# SparkaAway.net
KiCad netlist of a schematic drawn in Altium Designer
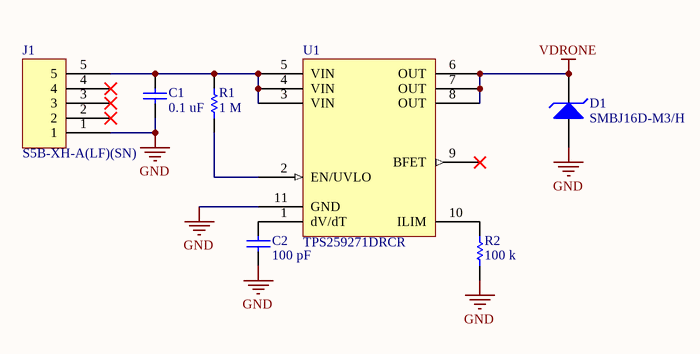
[diagram p0: SparkaAway.SchDoc]

(export (version "E")
  (design (tool "Eeschema 10.0.6"))
  (components
    (comp (ref "C1")
      (value "0.1 uF")
      (footprint "CAPC1608X10L")
      (description "CAP CER 0.1UF 50V X7R 0603")
      (fields
        (field (name "MANUFACTURER") "Samsung Electro-Mechanics America, Inc.")
        (field (name "MANUFACTURER PART NUMBER") "CL10B104MB8NNNC")
      )
      (libsource (lib "Componentes") (part "CL10B104MB8NNNC"))
    )
    (comp (ref "C2")
      (value "100 pF")
      (footprint "CAPC1608X10L")
      (description "Multilayer Ceramic Capacitors MLCC - SMD/SMT 0603 100pF 50volts C0G 5% T=0.8mm")
      (fields
        (field (name "MANUFACTURER") "TDK")
        (field (name "MANUFACTURER PART NUMBER") "CGA3E2C0G1H101J080AA")
      )
      (libsource (lib "Componentes") (part "CGA3E2C0G1H101J080AA"))
    )
    (comp (ref "D1")
      (value "SMBJ16D-M3/H")
      (footprint "DO-214AA SMB DIOM4336X24N")
      (description "TVS DIODE 16VWM 25.6VC DO214AA")
      (fields (field (name "MANUFACTURER") "Vishay Semiconductor Diodes Division"))
      (libsource (lib "SparkAway") (part "SMBJ16D-M3/H"))
    )
    (comp (ref "J1")
      (value "S5B-XH-A(LF)(SN)")
      (footprint "S5B-XH-A(LF)(SN)")
      (description "CONN HEADER XH SIDE 5POS 2.5MM")
      (fields (field (name "MANUFACTURER") "JST Sales America Inc."))
      (libsource (lib "SparkAway") (part "S5B-XH-A(LF)(SN)"))
    )
    (comp (ref "R1")
      (value "1 M")
      (footprint "RESC1608X05N")
      (description "Thick Film Resistors - SMD 1/10watt 1.0Mohms 1%")
      (fields
        (field (name "MANUFACTURER") "Vishay / Dale")
        (field (name "MANUFACTURER PART NUMBER") "CRCW06031M00FKEA")
      )
      (libsource (lib "Componentes") (part "CRCW06031M00FKEA"))
    )
    (comp (ref "R2")
      (value "100 k")
      (footprint "RESC1608X05N")
      (description "Thick Film Resistors - SMD 1/10watt 100Kohms 1%")
      (fields
        (field (name "MANUFACTURER") "Vishay / Dale")
        (field (name "MANUFACTURER PART NUMBER") "CRCW0603100KFKEA")
      )
      (libsource (lib "Componentes") (part "CRCW0603100KFKEA"))
    )
    (comp (ref "U1")
      (value "TPS259271DRCR")
      (footprint "TI S-PVSON-N10 SON50P300X100_HS-11N")
      (description "IC EFUSE 18V BFET DVR 5A 10VSON")
      (fields (field (name "MANUFACTURER") "Texas Instruments"))
      (libsource (lib "SparkAway") (part "TPS259271DRCR"))
    )
  )
  (nets
    (net (code "1") (name "GND") (class "Default")
      (node (ref "C1") (pin "1") (pinfunction "1_1") (pintype "passive"))
      (node (ref "C2") (pin "1") (pinfunction "1_1") (pintype "passive"))
      (node (ref "D1") (pin "2") (pinfunction "A_2") (pintype "passive"))
      (node (ref "J1") (pin "1") (pinfunction "1_1") (pintype "passive"))
      (node (ref "R2") (pin "1") (pinfunction "1_1") (pintype "passive"))
      (node (ref "U1") (pin "11") (pinfunction "GND_11") (pintype "power_in"))
    )
    (net (code "2") (name "Net-(C1-Pad2)") (class "Default")
      (node (ref "C1") (pin "2") (pinfunction "2_2") (pintype "passive"))
      (node (ref "J1") (pin "5") (pinfunction "5_5") (pintype "passive"))
      (node (ref "R1") (pin "2") (pinfunction "2_2") (pintype "passive"))
      (node (ref "U1") (pin "3") (pinfunction "VIN_3") (pintype "power_in"))
      (node (ref "U1") (pin "4") (pinfunction "VIN_4") (pintype "power_in"))
      (node (ref "U1") (pin "5") (pinfunction "VIN_5") (pintype "power_in"))
    )
    (net (code "3") (name "Net-(U1-EN{slash}UVLO)") (class "Default")
      (node (ref "R1") (pin "1") (pinfunction "1_1") (pintype "passive"))
      (node (ref "U1") (pin "2") (pinfunction "EN/UVLO_2") (pintype "input"))
    )
    (net (code "4") (name "Net-(U1-ILIM)") (class "Default")
      (node (ref "R2") (pin "2") (pinfunction "2_2") (pintype "passive"))
      (node (ref "U1") (pin "10") (pinfunction "ILIM_10") (pintype "passive"))
    )
    (net (code "5") (name "Net-(U1-dV{slash}dT)") (class "Default")
      (node (ref "C2") (pin "2") (pinfunction "2_2") (pintype "passive"))
      (node (ref "U1") (pin "1") (pinfunction "dV/dT_1") (pintype "passive"))
    )
    (net (code "6") (name "VDRONE") (class "Default")
      (node (ref "D1") (pin "1") (pinfunction "K_1") (pintype "passive"))
      (node (ref "U1") (pin "6") (pinfunction "OUT_6") (pintype "power_in"))
      (node (ref "U1") (pin "7") (pinfunction "OUT_7") (pintype "power_in"))
      (node (ref "U1") (pin "8") (pinfunction "OUT_8") (pintype "power_in"))
    )
    (net (code "7") (name "unconnected-(J1-Pad2)") (class "Default")
      (node (ref "J1") (pin "2") (pinfunction "2_2") (pintype "passive+no_connect"))
    )
    (net (code "8") (name "unconnected-(J1-Pad3)") (class "Default")
      (node (ref "J1") (pin "3") (pinfunction "3_3") (pintype "passive+no_connect"))
    )
    (net (code "9") (name "unconnected-(J1-Pad4)") (class "Default")
      (node (ref "J1") (pin "4") (pinfunction "4_4") (pintype "passive+no_connect"))
    )
    (net (code "10") (name "unconnected-(U1-BFET-Pad9)") (class "Default")
      (node (ref "U1") (pin "9") (pinfunction "BFET_9") (pintype "output+no_connect"))
    )
  )
)
